# ProProject_IR_sensor_board_2024-06-21.net
KiCad netlist of a schematic drawn in EasyEDA Pro
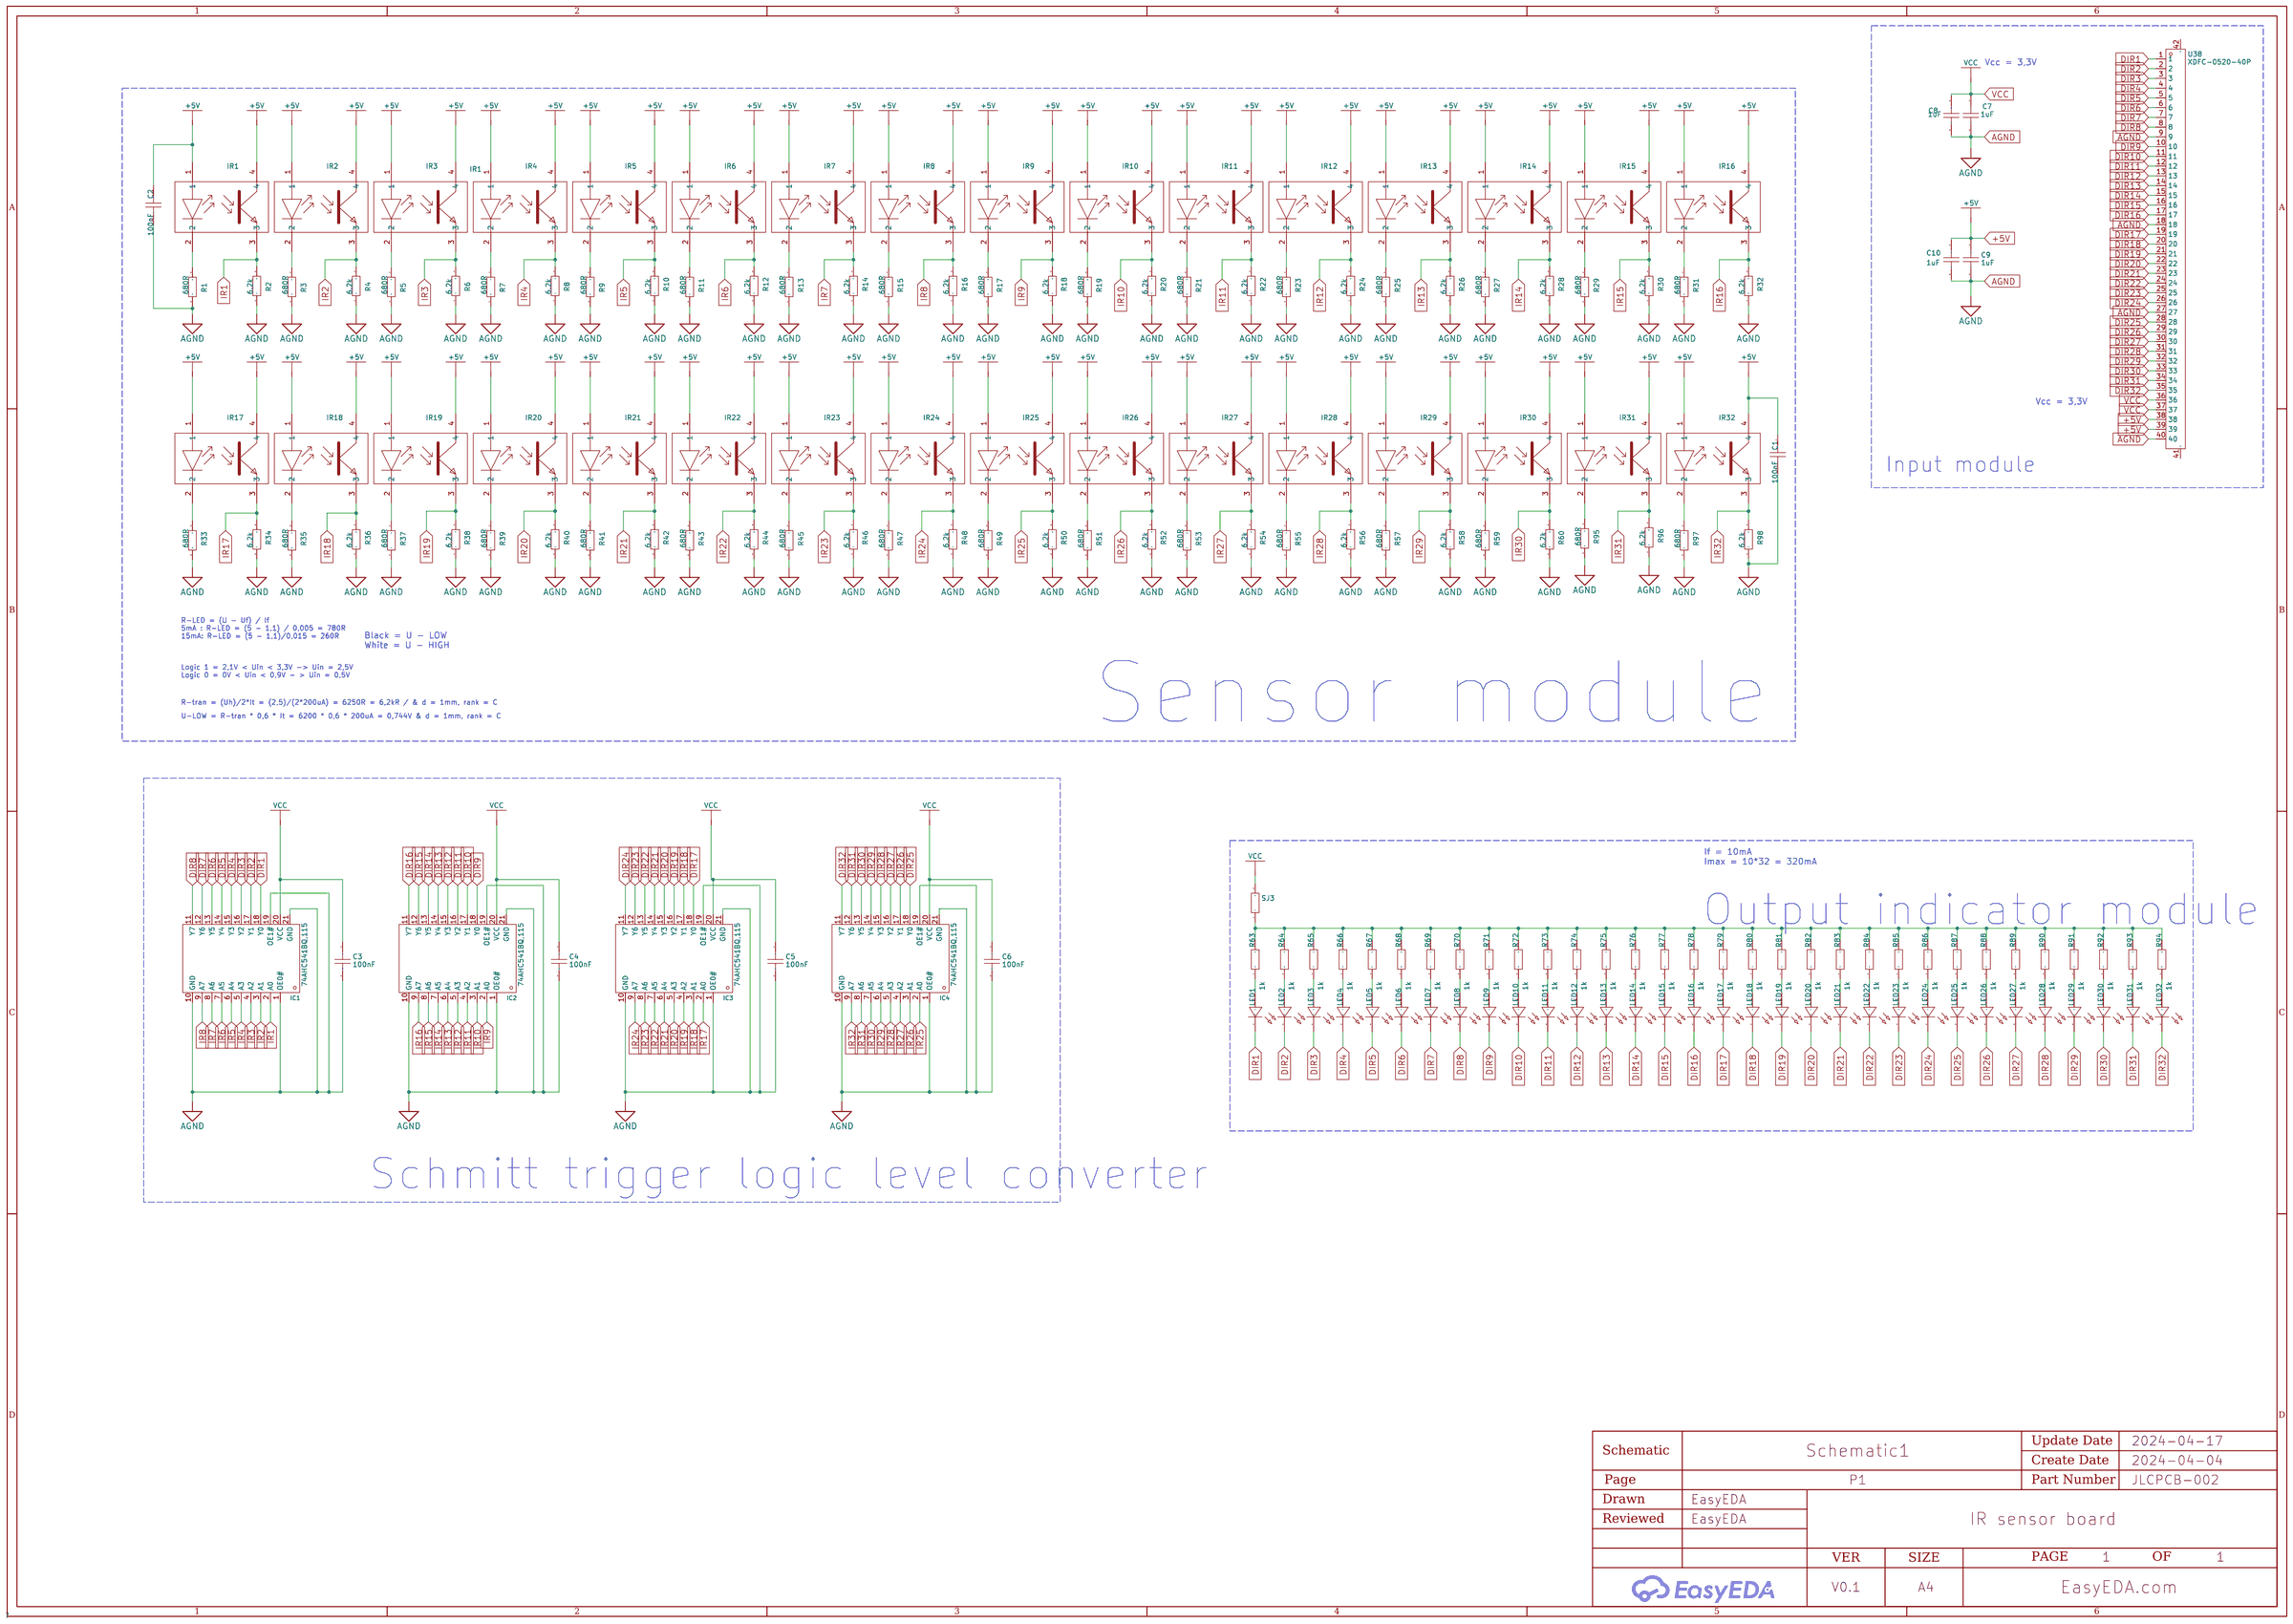
[diagram p0: schematic sheet]

(export (version "E")
  (design (tool "Eeschema 10.0.6"))
  (components
    (comp (ref "C1")
      (value "100nF")
      (footprint "easyedapro:C0603")
      (libsource (lib "easyedapro") (part "CAP"))
    )
    (comp (ref "C2")
      (value "100nF")
      (footprint "easyedapro:C0603")
      (libsource (lib "easyedapro") (part "CAP"))
    )
    (comp (ref "C3")
      (value "100nF")
      (footprint "easyedapro:C0603")
      (libsource (lib "easyedapro") (part "CAP"))
    )
    (comp (ref "C4")
      (value "100nF")
      (footprint "easyedapro:C0603")
      (libsource (lib "easyedapro") (part "CAP"))
    )
    (comp (ref "C5")
      (value "100nF")
      (footprint "easyedapro:C0603")
      (libsource (lib "easyedapro") (part "CAP"))
    )
    (comp (ref "C6")
      (value "100nF")
      (footprint "easyedapro:C0603")
      (libsource (lib "easyedapro") (part "CAP"))
    )
    (comp (ref "C7") (value "1uF") (footprint "easyedapro:C0603") (libsource (lib "easyedapro") (part "CAP")))
    (comp (ref "C8") (value "1uF") (footprint "easyedapro:C0603") (libsource (lib "easyedapro") (part "CAP")))
    (comp (ref "C9") (value "1uF") (footprint "easyedapro:C0603") (libsource (lib "easyedapro") (part "CAP")))
    (comp (ref "C10")
      (value "1uF")
      (footprint "easyedapro:C0603")
      (libsource (lib "easyedapro") (part "CAP"))
    )
    (comp (ref "IC1")
      (value "74AHC541BQ,115")
      (footprint "easyedapro:DHVQFN20_L4.5-W2.5-P0.50-BL-EP")
      (fields (field (name "Manufacturer") "Nexperia(安世)"))
      (libsource (lib "easyedapro") (part "74AHC541BQ,115"))
    )
    (comp (ref "IC2")
      (value "74AHC541BQ,115")
      (footprint "easyedapro:DHVQFN20_L4.5-W2.5-P0.50-BL-EP")
      (fields (field (name "Manufacturer") "Nexperia(安世)"))
      (libsource (lib "easyedapro") (part "74AHC541BQ,115"))
    )
    (comp (ref "IC3")
      (value "74AHC541BQ,115")
      (footprint "easyedapro:DHVQFN20_L4.5-W2.5-P0.50-BL-EP")
      (fields (field (name "Manufacturer") "Nexperia(安世)"))
      (libsource (lib "easyedapro") (part "74AHC541BQ,115"))
    )
    (comp (ref "IC4")
      (value "74AHC541BQ,115")
      (footprint "easyedapro:DHVQFN20_L4.5-W2.5-P0.50-BL-EP")
      (fields (field (name "Manufacturer") "Nexperia(安世)"))
      (libsource (lib "easyedapro") (part "74AHC541BQ,115"))
    )
    (comp (ref "IR1")
      (value "~")
      (footprint "easyedapro:KU163")
      (description "IR reflection sensor")
      (libsource (lib "easyedapro") (part "KU163"))
    )
    (comp (ref "IR2")
      (value "~")
      (footprint "easyedapro:KU163")
      (description "IR reflection sensor")
      (libsource (lib "easyedapro") (part "KU163"))
    )
    (comp (ref "IR3")
      (value "IR1")
      (footprint "easyedapro:KU163")
      (description "IR reflection sensor")
      (libsource (lib "easyedapro") (part "KU163"))
    )
    (comp (ref "IR4")
      (value "~")
      (footprint "easyedapro:KU163")
      (description "IR reflection sensor")
      (libsource (lib "easyedapro") (part "KU163"))
    )
    (comp (ref "IR5")
      (value "~")
      (footprint "easyedapro:KU163")
      (description "IR reflection sensor")
      (libsource (lib "easyedapro") (part "KU163"))
    )
    (comp (ref "IR6")
      (value "~")
      (footprint "easyedapro:KU163")
      (description "IR reflection sensor")
      (libsource (lib "easyedapro") (part "KU163"))
    )
    (comp (ref "IR7")
      (value "~")
      (footprint "easyedapro:KU163")
      (description "IR reflection sensor")
      (libsource (lib "easyedapro") (part "KU163"))
    )
    (comp (ref "IR8")
      (value "~")
      (footprint "easyedapro:KU163")
      (description "IR reflection sensor")
      (libsource (lib "easyedapro") (part "KU163"))
    )
    (comp (ref "IR9")
      (value "~")
      (footprint "easyedapro:KU163")
      (description "IR reflection sensor")
      (libsource (lib "easyedapro") (part "KU163"))
    )
    (comp (ref "IR10")
      (value "~")
      (footprint "easyedapro:KU163")
      (description "IR reflection sensor")
      (libsource (lib "easyedapro") (part "KU163"))
    )
    (comp (ref "IR11")
      (value "~")
      (footprint "easyedapro:KU163")
      (description "IR reflection sensor")
      (libsource (lib "easyedapro") (part "KU163"))
    )
    (comp (ref "IR12")
      (value "~")
      (footprint "easyedapro:KU163")
      (description "IR reflection sensor")
      (libsource (lib "easyedapro") (part "KU163"))
    )
    (comp (ref "IR13")
      (value "~")
      (footprint "easyedapro:KU163")
      (description "IR reflection sensor")
      (libsource (lib "easyedapro") (part "KU163"))
    )
    (comp (ref "IR14")
      (value "~")
      (footprint "easyedapro:KU163")
      (description "IR reflection sensor")
      (libsource (lib "easyedapro") (part "KU163"))
    )
    (comp (ref "IR15")
      (value "~")
      (footprint "easyedapro:KU163")
      (description "IR reflection sensor")
      (libsource (lib "easyedapro") (part "KU163"))
    )
    (comp (ref "IR16")
      (value "~")
      (footprint "easyedapro:KU163")
      (description "IR reflection sensor")
      (libsource (lib "easyedapro") (part "KU163"))
    )
    (comp (ref "IR17")
      (value "~")
      (footprint "easyedapro:KU163")
      (description "IR reflection sensor")
      (libsource (lib "easyedapro") (part "KU163"))
    )
    (comp (ref "IR18")
      (value "~")
      (footprint "easyedapro:KU163")
      (description "IR reflection sensor")
      (libsource (lib "easyedapro") (part "KU163"))
    )
    (comp (ref "IR19")
      (value "~")
      (footprint "easyedapro:KU163")
      (description "IR reflection sensor")
      (libsource (lib "easyedapro") (part "KU163"))
    )
    (comp (ref "IR20")
      (value "~")
      (footprint "easyedapro:KU163")
      (description "IR reflection sensor")
      (libsource (lib "easyedapro") (part "KU163"))
    )
    (comp (ref "IR21")
      (value "~")
      (footprint "easyedapro:KU163")
      (description "IR reflection sensor")
      (libsource (lib "easyedapro") (part "KU163"))
    )
    (comp (ref "IR22")
      (value "~")
      (footprint "easyedapro:KU163")
      (description "IR reflection sensor")
      (libsource (lib "easyedapro") (part "KU163"))
    )
    (comp (ref "IR23")
      (value "~")
      (footprint "easyedapro:KU163")
      (description "IR reflection sensor")
      (libsource (lib "easyedapro") (part "KU163"))
    )
    (comp (ref "IR24")
      (value "~")
      (footprint "easyedapro:KU163")
      (description "IR reflection sensor")
      (libsource (lib "easyedapro") (part "KU163"))
    )
    (comp (ref "IR25")
      (value "~")
      (footprint "easyedapro:KU163")
      (description "IR reflection sensor")
      (libsource (lib "easyedapro") (part "KU163"))
    )
    (comp (ref "IR26")
      (value "~")
      (footprint "easyedapro:KU163")
      (description "IR reflection sensor")
      (libsource (lib "easyedapro") (part "KU163"))
    )
    (comp (ref "IR27")
      (value "~")
      (footprint "easyedapro:KU163")
      (description "IR reflection sensor")
      (libsource (lib "easyedapro") (part "KU163"))
    )
    (comp (ref "IR28")
      (value "~")
      (footprint "easyedapro:KU163")
      (description "IR reflection sensor")
      (libsource (lib "easyedapro") (part "KU163"))
    )
    (comp (ref "IR29")
      (value "~")
      (footprint "easyedapro:KU163")
      (description "IR reflection sensor")
      (libsource (lib "easyedapro") (part "KU163"))
    )
    (comp (ref "IR30")
      (value "~")
      (footprint "easyedapro:KU163")
      (description "IR reflection sensor")
      (libsource (lib "easyedapro") (part "KU163"))
    )
    (comp (ref "IR31")
      (value "~")
      (footprint "easyedapro:KU163")
      (description "IR reflection sensor")
      (libsource (lib "easyedapro") (part "KU163"))
    )
    (comp (ref "IR32")
      (value "~")
      (footprint "easyedapro:KU163")
      (description "IR reflection sensor")
      (libsource (lib "easyedapro") (part "KU163"))
    )
    (comp (ref "LED1")
      (value "~")
      (footprint "easyedapro:LED0805-RD_GREEN")
      (libsource (lib "easyedapro") (part "LED_G"))
    )
    (comp (ref "LED2")
      (value "~")
      (footprint "easyedapro:LED0805-RD_GREEN")
      (libsource (lib "easyedapro") (part "LED_G"))
    )
    (comp (ref "LED3")
      (value "~")
      (footprint "easyedapro:LED0805-RD_GREEN")
      (libsource (lib "easyedapro") (part "LED_G"))
    )
    (comp (ref "LED4")
      (value "~")
      (footprint "easyedapro:LED0805-RD_GREEN")
      (libsource (lib "easyedapro") (part "LED_G"))
    )
    (comp (ref "LED5")
      (value "~")
      (footprint "easyedapro:LED0805-RD_GREEN")
      (libsource (lib "easyedapro") (part "LED_G"))
    )
    (comp (ref "LED6")
      (value "~")
      (footprint "easyedapro:LED0805-RD_GREEN")
      (libsource (lib "easyedapro") (part "LED_G"))
    )
    (comp (ref "LED7")
      (value "~")
      (footprint "easyedapro:LED0805-RD_GREEN")
      (libsource (lib "easyedapro") (part "LED_G"))
    )
    (comp (ref "LED8")
      (value "~")
      (footprint "easyedapro:LED0805-RD_GREEN")
      (libsource (lib "easyedapro") (part "LED_G"))
    )
    (comp (ref "LED9")
      (value "~")
      (footprint "easyedapro:LED0805-RD_GREEN")
      (libsource (lib "easyedapro") (part "LED_G"))
    )
    (comp (ref "LED10")
      (value "~")
      (footprint "easyedapro:LED0805-RD_GREEN")
      (libsource (lib "easyedapro") (part "LED_G"))
    )
    (comp (ref "LED11")
      (value "~")
      (footprint "easyedapro:LED0805-RD_GREEN")
      (libsource (lib "easyedapro") (part "LED_G"))
    )
    (comp (ref "LED12")
      (value "~")
      (footprint "easyedapro:LED0805-RD_GREEN")
      (libsource (lib "easyedapro") (part "LED_G"))
    )
    (comp (ref "LED13")
      (value "~")
      (footprint "easyedapro:LED0805-RD_GREEN")
      (libsource (lib "easyedapro") (part "LED_G"))
    )
    (comp (ref "LED14")
      (value "~")
      (footprint "easyedapro:LED0805-RD_GREEN")
      (libsource (lib "easyedapro") (part "LED_G"))
    )
    (comp (ref "LED15")
      (value "~")
      (footprint "easyedapro:LED0805-RD_GREEN")
      (libsource (lib "easyedapro") (part "LED_G"))
    )
    (comp (ref "LED16")
      (value "~")
      (footprint "easyedapro:LED0805-RD_GREEN")
      (libsource (lib "easyedapro") (part "LED_G"))
    )
    (comp (ref "LED17")
      (value "~")
      (footprint "easyedapro:LED0805-RD_GREEN")
      (libsource (lib "easyedapro") (part "LED_G"))
    )
    (comp (ref "LED18")
      (value "~")
      (footprint "easyedapro:LED0805-RD_GREEN")
      (libsource (lib "easyedapro") (part "LED_G"))
    )
    (comp (ref "LED19")
      (value "~")
      (footprint "easyedapro:LED0805-RD_GREEN")
      (libsource (lib "easyedapro") (part "LED_G"))
    )
    (comp (ref "LED20")
      (value "~")
      (footprint "easyedapro:LED0805-RD_GREEN")
      (libsource (lib "easyedapro") (part "LED_G"))
    )
    (comp (ref "LED21")
      (value "~")
      (footprint "easyedapro:LED0805-RD_GREEN")
      (libsource (lib "easyedapro") (part "LED_G"))
    )
    (comp (ref "LED22")
      (value "~")
      (footprint "easyedapro:LED0805-RD_GREEN")
      (libsource (lib "easyedapro") (part "LED_G"))
    )
    (comp (ref "LED23")
      (value "~")
      (footprint "easyedapro:LED0805-RD_GREEN")
      (libsource (lib "easyedapro") (part "LED_G"))
    )
    (comp (ref "LED24")
      (value "~")
      (footprint "easyedapro:LED0805-RD_GREEN")
      (libsource (lib "easyedapro") (part "LED_G"))
    )
    (comp (ref "LED25")
      (value "~")
      (footprint "easyedapro:LED0805-RD_GREEN")
      (libsource (lib "easyedapro") (part "LED_G"))
    )
    (comp (ref "LED26")
      (value "~")
      (footprint "easyedapro:LED0805-RD_GREEN")
      (libsource (lib "easyedapro") (part "LED_G"))
    )
    (comp (ref "LED27")
      (value "~")
      (footprint "easyedapro:LED0805-RD_GREEN")
      (libsource (lib "easyedapro") (part "LED_G"))
    )
    (comp (ref "LED28")
      (value "~")
      (footprint "easyedapro:LED0805-RD_GREEN")
      (libsource (lib "easyedapro") (part "LED_G"))
    )
    (comp (ref "LED29")
      (value "~")
      (footprint "easyedapro:LED0805-RD_GREEN")
      (libsource (lib "easyedapro") (part "LED_G"))
    )
    (comp (ref "LED30")
      (value "~")
      (footprint "easyedapro:LED0805-RD_GREEN")
      (libsource (lib "easyedapro") (part "LED_G"))
    )
    (comp (ref "LED31")
      (value "~")
      (footprint "easyedapro:LED0805-RD_GREEN")
      (libsource (lib "easyedapro") (part "LED_G"))
    )
    (comp (ref "LED32")
      (value "~")
      (footprint "easyedapro:LED0805-RD_GREEN")
      (libsource (lib "easyedapro") (part "LED_G"))
    )
    (comp (ref "R1")
      (value "680R")
      (footprint "easyedapro:R0603")
      (libsource (lib "easyedapro") (part "Res"))
    )
    (comp (ref "R2")
      (value "6.2k")
      (footprint "easyedapro:R0603")
      (libsource (lib "easyedapro") (part "Res"))
    )
    (comp (ref "R3")
      (value "680R")
      (footprint "easyedapro:R0603")
      (libsource (lib "easyedapro") (part "Res"))
    )
    (comp (ref "R4")
      (value "6.2k")
      (footprint "easyedapro:R0603")
      (libsource (lib "easyedapro") (part "Res"))
    )
    (comp (ref "R5")
      (value "680R")
      (footprint "easyedapro:R0603")
      (libsource (lib "easyedapro") (part "Res"))
    )
    (comp (ref "R6")
      (value "6.2k")
      (footprint "easyedapro:R0603")
      (libsource (lib "easyedapro") (part "Res"))
    )
    (comp (ref "R7")
      (value "680R")
      (footprint "easyedapro:R0603")
      (libsource (lib "easyedapro") (part "Res"))
    )
    (comp (ref "R8")
      (value "6.2k")
      (footprint "easyedapro:R0603")
      (libsource (lib "easyedapro") (part "Res"))
    )
    (comp (ref "R9")
      (value "680R")
      (footprint "easyedapro:R0603")
      (libsource (lib "easyedapro") (part "Res"))
    )
    (comp (ref "R10")
      (value "6.2k")
      (footprint "easyedapro:R0603")
      (libsource (lib "easyedapro") (part "Res"))
    )
    (comp (ref "R11")
      (value "680R")
      (footprint "easyedapro:R0603")
      (libsource (lib "easyedapro") (part "Res"))
    )
    (comp (ref "R12")
      (value "6.2k")
      (footprint "easyedapro:R0603")
      (libsource (lib "easyedapro") (part "Res"))
    )
    (comp (ref "R13")
      (value "680R")
      (footprint "easyedapro:R0603")
      (libsource (lib "easyedapro") (part "Res"))
    )
    (comp (ref "R14")
      (value "6.2k")
      (footprint "easyedapro:R0603")
      (libsource (lib "easyedapro") (part "Res"))
    )
    (comp (ref "R15")
      (value "680R")
      (footprint "easyedapro:R0603")
      (libsource (lib "easyedapro") (part "Res"))
    )
    (comp (ref "R16")
      (value "6.2k")
      (footprint "easyedapro:R0603")
      (libsource (lib "easyedapro") (part "Res"))
    )
    (comp (ref "R17")
      (value "680R")
      (footprint "easyedapro:R0603")
      (libsource (lib "easyedapro") (part "Res"))
    )
    (comp (ref "R18")
      (value "6.2k")
      (footprint "easyedapro:R0603")
      (libsource (lib "easyedapro") (part "Res"))
    )
    (comp (ref "R19")
      (value "680R")
      (footprint "easyedapro:R0603")
      (libsource (lib "easyedapro") (part "Res"))
    )
    (comp (ref "R20")
      (value "6.2k")
      (footprint "easyedapro:R0603")
      (libsource (lib "easyedapro") (part "Res"))
    )
    (comp (ref "R21")
      (value "680R")
      (footprint "easyedapro:R0603")
      (libsource (lib "easyedapro") (part "Res"))
    )
    (comp (ref "R22")
      (value "6.2k")
      (footprint "easyedapro:R0603")
      (libsource (lib "easyedapro") (part "Res"))
    )
    (comp (ref "R23")
      (value "680R")
      (footprint "easyedapro:R0603")
      (libsource (lib "easyedapro") (part "Res"))
    )
    (comp (ref "R24")
      (value "6.2k")
      (footprint "easyedapro:R0603")
      (libsource (lib "easyedapro") (part "Res"))
    )
    (comp (ref "R25")
      (value "680R")
      (footprint "easyedapro:R0603")
      (libsource (lib "easyedapro") (part "Res"))
    )
    (comp (ref "R26")
      (value "6.2k")
      (footprint "easyedapro:R0603")
      (libsource (lib "easyedapro") (part "Res"))
    )
    (comp (ref "R27")
      (value "680R")
      (footprint "easyedapro:R0603")
      (libsource (lib "easyedapro") (part "Res"))
    )
    (comp (ref "R28")
      (value "6.2k")
      (footprint "easyedapro:R0603")
      (libsource (lib "easyedapro") (part "Res"))
    )
    (comp (ref "R29")
      (value "680R")
      (footprint "easyedapro:R0603")
      (libsource (lib "easyedapro") (part "Res"))
    )
    (comp (ref "R30")
      (value "6.2k")
      (footprint "easyedapro:R0603")
      (libsource (lib "easyedapro") (part "Res"))
    )
    (comp (ref "R31")
      (value "680R")
      (footprint "easyedapro:R0603")
      (libsource (lib "easyedapro") (part "Res"))
    )
    (comp (ref "R32")
      (value "6.2k")
      (footprint "easyedapro:R0603")
      (libsource (lib "easyedapro") (part "Res"))
    )
    (comp (ref "R33")
      (value "680R")
      (footprint "easyedapro:R0603")
      (libsource (lib "easyedapro") (part "Res"))
    )
    (comp (ref "R34")
      (value "6.2k")
      (footprint "easyedapro:R0603")
      (libsource (lib "easyedapro") (part "Res"))
    )
    (comp (ref "R35")
      (value "680R")
      (footprint "easyedapro:R0603")
      (libsource (lib "easyedapro") (part "Res"))
    )
    (comp (ref "R36")
      (value "6.2k")
      (footprint "easyedapro:R0603")
      (libsource (lib "easyedapro") (part "Res"))
    )
    (comp (ref "R37")
      (value "680R")
      (footprint "easyedapro:R0603")
      (libsource (lib "easyedapro") (part "Res"))
    )
    (comp (ref "R38")
      (value "6.2k")
      (footprint "easyedapro:R0603")
      (libsource (lib "easyedapro") (part "Res"))
    )
    (comp (ref "R39")
      (value "680R")
      (footprint "easyedapro:R0603")
      (libsource (lib "easyedapro") (part "Res"))
    )
    (comp (ref "R40")
      (value "6.2k")
      (footprint "easyedapro:R0603")
      (libsource (lib "easyedapro") (part "Res"))
    )
    (comp (ref "R41")
      (value "680R")
      (footprint "easyedapro:R0603")
      (libsource (lib "easyedapro") (part "Res"))
    )
    (comp (ref "R42")
      (value "6.2k")
      (footprint "easyedapro:R0603")
      (libsource (lib "easyedapro") (part "Res"))
    )
    (comp (ref "R43")
      (value "680R")
      (footprint "easyedapro:R0603")
      (libsource (lib "easyedapro") (part "Res"))
    )
    (comp (ref "R44")
      (value "6.2k")
      (footprint "easyedapro:R0603")
      (libsource (lib "easyedapro") (part "Res"))
    )
    (comp (ref "R45")
      (value "680R")
      (footprint "easyedapro:R0603")
      (libsource (lib "easyedapro") (part "Res"))
    )
    (comp (ref "R46")
      (value "6.2k")
      (footprint "easyedapro:R0603")
      (libsource (lib "easyedapro") (part "Res"))
    )
    (comp (ref "R47")
      (value "680R")
      (footprint "easyedapro:R0603")
      (libsource (lib "easyedapro") (part "Res"))
    )
    (comp (ref "R48")
      (value "6.2k")
      (footprint "easyedapro:R0603")
      (libsource (lib "easyedapro") (part "Res"))
    )
    (comp (ref "R49")
      (value "680R")
      (footprint "easyedapro:R0603")
      (libsource (lib "easyedapro") (part "Res"))
    )
    (comp (ref "R50")
      (value "6.2k")
      (footprint "easyedapro:R0603")
      (libsource (lib "easyedapro") (part "Res"))
    )
    (comp (ref "R51")
      (value "680R")
      (footprint "easyedapro:R0603")
      (libsource (lib "easyedapro") (part "Res"))
    )
    (comp (ref "R52")
      (value "6.2k")
      (footprint "easyedapro:R0603")
      (libsource (lib "easyedapro") (part "Res"))
    )
    (comp (ref "R53")
      (value "680R")
      (footprint "easyedapro:R0603")
      (libsource (lib "easyedapro") (part "Res"))
    )
    (comp (ref "R54")
      (value "6.2k")
      (footprint "easyedapro:R0603")
      (libsource (lib "easyedapro") (part "Res"))
    )
    (comp (ref "R55")
      (value "680R")
      (footprint "easyedapro:R0603")
      (libsource (lib "easyedapro") (part "Res"))
    )
    (comp (ref "R56")
      (value "6.2k")
      (footprint "easyedapro:R0603")
      (libsource (lib "easyedapro") (part "Res"))
    )
    (comp (ref "R57")
      (value "680R")
      (footprint "easyedapro:R0603")
      (libsource (lib "easyedapro") (part "Res"))
    )
    (comp (ref "R58")
      (value "6.2k")
      (footprint "easyedapro:R0603")
      (libsource (lib "easyedapro") (part "Res"))
    )
    (comp (ref "R59")
      (value "680R")
      (footprint "easyedapro:R0603")
      (libsource (lib "easyedapro") (part "Res"))
    )
    (comp (ref "R60")
      (value "6.2k")
      (footprint "easyedapro:R0603")
      (libsource (lib "easyedapro") (part "Res"))
    )
    (comp (ref "R63") (value "1k") (footprint "easyedapro:R0603") (libsource (lib "easyedapro") (part "Res")))
    (comp (ref "R64") (value "1k") (footprint "easyedapro:R0603") (libsource (lib "easyedapro") (part "Res")))
    (comp (ref "R65") (value "1k") (footprint "easyedapro:R0603") (libsource (lib "easyedapro") (part "Res")))
    (comp (ref "R66") (value "1k") (footprint "easyedapro:R0603") (libsource (lib "easyedapro") (part "Res")))
    (comp (ref "R67") (value "1k") (footprint "easyedapro:R0603") (libsource (lib "easyedapro") (part "Res")))
    (comp (ref "R68") (value "1k") (footprint "easyedapro:R0603") (libsource (lib "easyedapro") (part "Res")))
    (comp (ref "R69") (value "1k") (footprint "easyedapro:R0603") (libsource (lib "easyedapro") (part "Res")))
    (comp (ref "R70") (value "1k") (footprint "easyedapro:R0603") (libsource (lib "easyedapro") (part "Res")))
    (comp (ref "R71") (value "1k") (footprint "easyedapro:R0603") (libsource (lib "easyedapro") (part "Res")))
    (comp (ref "R72") (value "1k") (footprint "easyedapro:R0603") (libsource (lib "easyedapro") (part "Res")))
    (comp (ref "R73") (value "1k") (footprint "easyedapro:R0603") (libsource (lib "easyedapro") (part "Res")))
    (comp (ref "R74") (value "1k") (footprint "easyedapro:R0603") (libsource (lib "easyedapro") (part "Res")))
    (comp (ref "R75") (value "1k") (footprint "easyedapro:R0603") (libsource (lib "easyedapro") (part "Res")))
    (comp (ref "R76") (value "1k") (footprint "easyedapro:R0603") (libsource (lib "easyedapro") (part "Res")))
    (comp (ref "R77") (value "1k") (footprint "easyedapro:R0603") (libsource (lib "easyedapro") (part "Res")))
    (comp (ref "R78") (value "1k") (footprint "easyedapro:R0603") (libsource (lib "easyedapro") (part "Res")))
    (comp (ref "R79") (value "1k") (footprint "easyedapro:R0603") (libsource (lib "easyedapro") (part "Res")))
    (comp (ref "R80") (value "1k") (footprint "easyedapro:R0603") (libsource (lib "easyedapro") (part "Res")))
    (comp (ref "R81") (value "1k") (footprint "easyedapro:R0603") (libsource (lib "easyedapro") (part "Res")))
    (comp (ref "R82") (value "1k") (footprint "easyedapro:R0603") (libsource (lib "easyedapro") (part "Res")))
    (comp (ref "R83") (value "1k") (footprint "easyedapro:R0603") (libsource (lib "easyedapro") (part "Res")))
    (comp (ref "R84") (value "1k") (footprint "easyedapro:R0603") (libsource (lib "easyedapro") (part "Res")))
    (comp (ref "R85") (value "1k") (footprint "easyedapro:R0603") (libsource (lib "easyedapro") (part "Res")))
    (comp (ref "R86") (value "1k") (footprint "easyedapro:R0603") (libsource (lib "easyedapro") (part "Res")))
    (comp (ref "R87") (value "1k") (footprint "easyedapro:R0603") (libsource (lib "easyedapro") (part "Res")))
    (comp (ref "R88") (value "1k") (footprint "easyedapro:R0603") (libsource (lib "easyedapro") (part "Res")))
    (comp (ref "R89") (value "1k") (footprint "easyedapro:R0603") (libsource (lib "easyedapro") (part "Res")))
    (comp (ref "R90") (value "1k") (footprint "easyedapro:R0603") (libsource (lib "easyedapro") (part "Res")))
    (comp (ref "R91") (value "1k") (footprint "easyedapro:R0603") (libsource (lib "easyedapro") (part "Res")))
    (comp (ref "R92") (value "1k") (footprint "easyedapro:R0603") (libsource (lib "easyedapro") (part "Res")))
    (comp (ref "R93") (value "1k") (footprint "easyedapro:R0603") (libsource (lib "easyedapro") (part "Res")))
    (comp (ref "R94") (value "1k") (footprint "easyedapro:R0603") (libsource (lib "easyedapro") (part "Res")))
    (comp (ref "R95")
      (value "680R")
      (footprint "easyedapro:R0603")
      (libsource (lib "easyedapro") (part "Res"))
    )
    (comp (ref "R96")
      (value "6.2k")
      (footprint "easyedapro:R0603")
      (libsource (lib "easyedapro") (part "Res"))
    )
    (comp (ref "R97")
      (value "680R")
      (footprint "easyedapro:R0603")
      (libsource (lib "easyedapro") (part "Res"))
    )
    (comp (ref "R98")
      (value "6.2k")
      (footprint "easyedapro:R0603")
      (libsource (lib "easyedapro") (part "Res"))
    )
    (comp (ref "SJ3")
      (value "10K")
      (footprint "easyedapro:R0603")
      (libsource (lib "easyedapro") (part "Res"))
    )
    (comp (ref "U38")
      (value "XDFC-0520-40P")
      (footprint "easyedapro:FPC-SMD_40P-P0.50_XDFC-0520-40P")
      (fields (field (name "Manufacturer") "LX(连欣科技)"))
      (libsource (lib "easyedapro") (part "XDFC-0520-40P"))
    )
  )
  (nets
    (net (code "1") (name "+5V") (class "Default")
      (node (ref "C1") (pin "1") (pinfunction "1_1") (pintype "input"))
      (node (ref "C10") (pin "1") (pinfunction "1_1") (pintype "input"))
      (node (ref "C2") (pin "1") (pinfunction "1_1") (pintype "input"))
      (node (ref "C9") (pin "1") (pinfunction "1_1") (pintype "input"))
      (node (ref "IR1") (pin "1") (pinfunction "1_1") (pintype "input"))
      (node (ref "IR1") (pin "4") (pinfunction "4_4") (pintype "input"))
      (node (ref "IR10") (pin "1") (pinfunction "1_1") (pintype "input"))
      (node (ref "IR10") (pin "4") (pinfunction "4_4") (pintype "input"))
      (node (ref "IR11") (pin "1") (pinfunction "1_1") (pintype "input"))
      (node (ref "IR11") (pin "4") (pinfunction "4_4") (pintype "input"))
      (node (ref "IR12") (pin "1") (pinfunction "1_1") (pintype "input"))
      (node (ref "IR12") (pin "4") (pinfunction "4_4") (pintype "input"))
      (node (ref "IR13") (pin "1") (pinfunction "1_1") (pintype "input"))
      (node (ref "IR13") (pin "4") (pinfunction "4_4") (pintype "input"))
      (node (ref "IR14") (pin "1") (pinfunction "1_1") (pintype "input"))
      (node (ref "IR14") (pin "4") (pinfunction "4_4") (pintype "input"))
      (node (ref "IR15") (pin "1") (pinfunction "1_1") (pintype "input"))
      (node (ref "IR15") (pin "4") (pinfunction "4_4") (pintype "input"))
      (node (ref "IR16") (pin "1") (pinfunction "1_1") (pintype "input"))
      (node (ref "IR16") (pin "4") (pinfunction "4_4") (pintype "input"))
      (node (ref "IR17") (pin "1") (pinfunction "1_1") (pintype "input"))
      (node (ref "IR17") (pin "4") (pinfunction "4_4") (pintype "input"))
      (node (ref "IR18") (pin "1") (pinfunction "1_1") (pintype "input"))
      (node (ref "IR18") (pin "4") (pinfunction "4_4") (pintype "input"))
      (node (ref "IR19") (pin "1") (pinfunction "1_1") (pintype "input"))
      (node (ref "IR19") (pin "4") (pinfunction "4_4") (pintype "input"))
      (node (ref "IR2") (pin "1") (pinfunction "1_1") (pintype "input"))
      (node (ref "IR2") (pin "4") (pinfunction "4_4") (pintype "input"))
      (node (ref "IR20") (pin "1") (pinfunction "1_1") (pintype "input"))
      (node (ref "IR20") (pin "4") (pinfunction "4_4") (pintype "input"))
      (node (ref "IR21") (pin "1") (pinfunction "1_1") (pintype "input"))
      (node (ref "IR21") (pin "4") (pinfunction "4_4") (pintype "input"))
      (node (ref "IR22") (pin "1") (pinfunction "1_1") (pintype "input"))
      (node (ref "IR22") (pin "4") (pinfunction "4_4") (pintype "input"))
      (node (ref "IR23") (pin "1") (pinfunction "1_1") (pintype "input"))
      (node (ref "IR23") (pin "4") (pinfunction "4_4") (pintype "input"))
      (node (ref "IR24") (pin "1") (pinfunction "1_1") (pintype "input"))
      (node (ref "IR24") (pin "4") (pinfunction "4_4") (pintype "input"))
      (node (ref "IR25") (pin "1") (pinfunction "1_1") (pintype "input"))
      (node (ref "IR25") (pin "4") (pinfunction "4_4") (pintype "input"))
      (node (ref "IR26") (pin "1") (pinfunction "1_1") (pintype "input"))
      (node (ref "IR26") (pin "4") (pinfunction "4_4") (pintype "input"))
      (node (ref "IR27") (pin "1") (pinfunction "1_1") (pintype "input"))
      (node (ref "IR27") (pin "4") (pinfunction "4_4") (pintype "input"))
      (node (ref "IR28") (pin "1") (pinfunction "1_1") (pintype "input"))
      (node (ref "IR28") (pin "4") (pinfunction "4_4") (pintype "input"))
      (node (ref "IR29") (pin "1") (pinfunction "1_1") (pintype "input"))
      (node (ref "IR29") (pin "4") (pinfunction "4_4") (pintype "input"))
      (node (ref "IR3") (pin "1") (pinfunction "1_1") (pintype "input"))
      (node (ref "IR3") (pin "4") (pinfunction "4_4") (pintype "input"))
      (node (ref "IR30") (pin "1") (pinfunction "1_1") (pintype "input"))
      (node (ref "IR30") (pin "4") (pinfunction "4_4") (pintype "input"))
      (node (ref "IR31") (pin "1") (pinfunction "1_1") (pintype "input"))
      (node (ref "IR31") (pin "4") (pinfunction "4_4") (pintype "input"))
      (node (ref "IR32") (pin "1") (pinfunction "1_1") (pintype "input"))
      (node (ref "IR32") (pin "4") (pinfunction "4_4") (pintype "input"))
      (node (ref "IR4") (pin "1") (pinfunction "1_1") (pintype "input"))
      (node (ref "IR4") (pin "4") (pinfunction "4_4") (pintype "input"))
      (node (ref "IR5") (pin "1") (pinfunction "1_1") (pintype "input"))
      (node (ref "IR5") (pin "4") (pinfunction "4_4") (pintype "input"))
      (node (ref "IR6") (pin "1") (pinfunction "1_1") (pintype "input"))
      (node (ref "IR6") (pin "4") (pinfunction "4_4") (pintype "input"))
      (node (ref "IR7") (pin "1") (pinfunction "1_1") (pintype "input"))
      (node (ref "IR7") (pin "4") (pinfunction "4_4") (pintype "input"))
      (node (ref "IR8") (pin "1") (pinfunction "1_1") (pintype "input"))
      (node (ref "IR8") (pin "4") (pinfunction "4_4") (pintype "input"))
      (node (ref "IR9") (pin "1") (pinfunction "1_1") (pintype "input"))
      (node (ref "IR9") (pin "4") (pinfunction "4_4") (pintype "input"))
      (node (ref "U38") (pin "38") (pinfunction "38_38") (pintype "unspecified"))
      (node (ref "U38") (pin "39") (pinfunction "39_39") (pintype "unspecified"))
    )
    (net (code "2") (name "AGND") (class "Default")
      (node (ref "C1") (pin "2") (pinfunction "2_2") (pintype "input"))
      (node (ref "C10") (pin "2") (pinfunction "2_2") (pintype "input"))
      (node (ref "C2") (pin "2") (pinfunction "2_2") (pintype "input"))
      (node (ref "C3") (pin "2") (pinfunction "2_2") (pintype "input"))
      (node (ref "C4") (pin "2") (pinfunction "2_2") (pintype "input"))
      (node (ref "C5") (pin "2") (pinfunction "2_2") (pintype "input"))
      (node (ref "C6") (pin "2") (pinfunction "2_2") (pintype "input"))
      (node (ref "C7") (pin "2") (pinfunction "2_2") (pintype "input"))
      (node (ref "C8") (pin "2") (pinfunction "2_2") (pintype "input"))
      (node (ref "C9") (pin "2") (pinfunction "2_2") (pintype "input"))
      (node (ref "IC1") (pin "1") (pinfunction "OE0#_1") (pintype "input"))
      (node (ref "IC1") (pin "10") (pinfunction "GND_10") (pintype "input"))
      (node (ref "IC1") (pin "19") (pinfunction "OE1#_19") (pintype "input"))
      (node (ref "IC1") (pin "21") (pinfunction "GND_21") (pintype "input"))
      (node (ref "IC2") (pin "1") (pinfunction "OE0#_1") (pintype "input"))
      (node (ref "IC2") (pin "10") (pinfunction "GND_10") (pintype "input"))
      (node (ref "IC2") (pin "19") (pinfunction "OE1#_19") (pintype "input"))
      (node (ref "IC2") (pin "21") (pinfunction "GND_21") (pintype "input"))
      (node (ref "IC3") (pin "1") (pinfunction "OE0#_1") (pintype "input"))
      (node (ref "IC3") (pin "10") (pinfunction "GND_10") (pintype "input"))
      (node (ref "IC3") (pin "19") (pinfunction "OE1#_19") (pintype "input"))
      (node (ref "IC3") (pin "21") (pinfunction "GND_21") (pintype "input"))
      (node (ref "IC4") (pin "1") (pinfunction "OE0#_1") (pintype "input"))
      (node (ref "IC4") (pin "10") (pinfunction "GND_10") (pintype "input"))
      (node (ref "IC4") (pin "19") (pinfunction "OE1#_19") (pintype "input"))
      (node (ref "IC4") (pin "21") (pinfunction "GND_21") (pintype "input"))
      (node (ref "R1") (pin "2") (pinfunction "2_2") (pintype "input"))
      (node (ref "R10") (pin "1") (pinfunction "1_1") (pintype "input"))
      (node (ref "R11") (pin "2") (pinfunction "2_2") (pintype "input"))
      (node (ref "R12") (pin "1") (pinfunction "1_1") (pintype "input"))
      (node (ref "R13") (pin "2") (pinfunction "2_2") (pintype "input"))
      (node (ref "R14") (pin "1") (pinfunction "1_1") (pintype "input"))
      (node (ref "R15") (pin "2") (pinfunction "2_2") (pintype "input"))
      (node (ref "R16") (pin "1") (pinfunction "1_1") (pintype "input"))
      (node (ref "R17") (pin "2") (pinfunction "2_2") (pintype "input"))
      (node (ref "R18") (pin "1") (pinfunction "1_1") (pintype "input"))
      (node (ref "R19") (pin "2") (pinfunction "2_2") (pintype "input"))
      (node (ref "R2") (pin "1") (pinfunction "1_1") (pintype "input"))
      (node (ref "R20") (pin "1") (pinfunction "1_1") (pintype "input"))
      (node (ref "R21") (pin "2") (pinfunction "2_2") (pintype "input"))
      (node (ref "R22") (pin "1") (pinfunction "1_1") (pintype "input"))
      (node (ref "R23") (pin "2") (pinfunction "2_2") (pintype "input"))
      (node (ref "R24") (pin "1") (pinfunction "1_1") (pintype "input"))
      (node (ref "R25") (pin "2") (pinfunction "2_2") (pintype "input"))
      (node (ref "R26") (pin "1") (pinfunction "1_1") (pintype "input"))
      (node (ref "R27") (pin "2") (pinfunction "2_2") (pintype "input"))
      (node (ref "R28") (pin "1") (pinfunction "1_1") (pintype "input"))
      (node (ref "R29") (pin "2") (pinfunction "2_2") (pintype "input"))
      (node (ref "R3") (pin "2") (pinfunction "2_2") (pintype "input"))
      (node (ref "R30") (pin "1") (pinfunction "1_1") (pintype "input"))
      (node (ref "R31") (pin "2") (pinfunction "2_2") (pintype "input"))
      (node (ref "R32") (pin "1") (pinfunction "1_1") (pintype "input"))
      (node (ref "R33") (pin "2") (pinfunction "2_2") (pintype "input"))
      (node (ref "R34") (pin "1") (pinfunction "1_1") (pintype "input"))
      (node (ref "R35") (pin "2") (pinfunction "2_2") (pintype "input"))
      (node (ref "R36") (pin "1") (pinfunction "1_1") (pintype "input"))
      (node (ref "R37") (pin "2") (pinfunction "2_2") (pintype "input"))
      (node (ref "R38") (pin "1") (pinfunction "1_1") (pintype "input"))
      (node (ref "R39") (pin "2") (pinfunction "2_2") (pintype "input"))
      (node (ref "R4") (pin "1") (pinfunction "1_1") (pintype "input"))
      (node (ref "R40") (pin "1") (pinfunction "1_1") (pintype "input"))
      (node (ref "R41") (pin "2") (pinfunction "2_2") (pintype "input"))
      (node (ref "R42") (pin "1") (pinfunction "1_1") (pintype "input"))
      (node (ref "R43") (pin "2") (pinfunction "2_2") (pintype "input"))
      (node (ref "R44") (pin "1") (pinfunction "1_1") (pintype "input"))
      (node (ref "R45") (pin "2") (pinfunction "2_2") (pintype "input"))
      (node (ref "R46") (pin "1") (pinfunction "1_1") (pintype "input"))
      (node (ref "R47") (pin "2") (pinfunction "2_2") (pintype "input"))
      (node (ref "R48") (pin "1") (pinfunction "1_1") (pintype "input"))
      (node (ref "R49") (pin "2") (pinfunction "2_2") (pintype "input"))
      (node (ref "R5") (pin "2") (pinfunction "2_2") (pintype "input"))
      (node (ref "R50") (pin "1") (pinfunction "1_1") (pintype "input"))
      (node (ref "R51") (pin "2") (pinfunction "2_2") (pintype "input"))
      (node (ref "R52") (pin "1") (pinfunction "1_1") (pintype "input"))
      (node (ref "R53") (pin "2") (pinfunction "2_2") (pintype "input"))
      (node (ref "R54") (pin "1") (pinfunction "1_1") (pintype "input"))
      (node (ref "R55") (pin "2") (pinfunction "2_2") (pintype "input"))
      (node (ref "R56") (pin "1") (pinfunction "1_1") (pintype "input"))
      (node (ref "R57") (pin "2") (pinfunction "2_2") (pintype "input"))
      (node (ref "R58") (pin "1") (pinfunction "1_1") (pintype "input"))
      (node (ref "R59") (pin "2") (pinfunction "2_2") (pintype "input"))
      (node (ref "R6") (pin "1") (pinfunction "1_1") (pintype "input"))
      (node (ref "R60") (pin "1") (pinfunction "1_1") (pintype "input"))
      (node (ref "R7") (pin "2") (pinfunction "2_2") (pintype "input"))
      (node (ref "R8") (pin "1") (pinfunction "1_1") (pintype "input"))
      (node (ref "R9") (pin "2") (pinfunction "2_2") (pintype "input"))
      (node (ref "R95") (pin "2") (pinfunction "2_2") (pintype "input"))
      (node (ref "R96") (pin "1") (pinfunction "1_1") (pintype "input"))
      (node (ref "R97") (pin "2") (pinfunction "2_2") (pintype "input"))
      (node (ref "R98") (pin "1") (pinfunction "1_1") (pintype "input"))
      (node (ref "U38") (pin "18") (pinfunction "18_18") (pintype "unspecified"))
      (node (ref "U38") (pin "27") (pinfunction "27_27") (pintype "unspecified"))
      (node (ref "U38") (pin "40") (pinfunction "40_40") (pintype "unspecified"))
      (node (ref "U38") (pin "9") (pinfunction "9_9") (pintype "unspecified"))
    )
    (net (code "3") (name "DIR1") (class "Default")
      (node (ref "IC1") (pin "18") (pinfunction "Y0_18") (pintype "input"))
      (node (ref "LED1") (pin "1") (pinfunction "C_1") (pintype "input"))
      (node (ref "U38") (pin "1") (pinfunction "1_1") (pintype "unspecified"))
    )
    (net (code "4") (name "DIR2") (class "Default")
      (node (ref "IC1") (pin "17") (pinfunction "Y1_17") (pintype "input"))
      (node (ref "LED2") (pin "1") (pinfunction "C_1") (pintype "input"))
      (node (ref "U38") (pin "2") (pinfunction "2_2") (pintype "unspecified"))
    )
    (net (code "5") (name "DIR3") (class "Default")
      (node (ref "IC1") (pin "16") (pinfunction "Y2_16") (pintype "input"))
      (node (ref "LED3") (pin "1") (pinfunction "C_1") (pintype "input"))
      (node (ref "U38") (pin "3") (pinfunction "3_3") (pintype "unspecified"))
    )
    (net (code "6") (name "DIR4") (class "Default")
      (node (ref "IC1") (pin "15") (pinfunction "Y3_15") (pintype "input"))
      (node (ref "LED4") (pin "1") (pinfunction "C_1") (pintype "input"))
      (node (ref "U38") (pin "4") (pinfunction "4_4") (pintype "unspecified"))
    )
    (net (code "7") (name "DIR5") (class "Default")
      (node (ref "IC1") (pin "14") (pinfunction "Y4_14") (pintype "input"))
      (node (ref "LED5") (pin "1") (pinfunction "C_1") (pintype "input"))
      (node (ref "U38") (pin "5") (pinfunction "5_5") (pintype "unspecified"))
    )
    (net (code "8") (name "DIR6") (class "Default")
      (node (ref "IC1") (pin "13") (pinfunction "Y5_13") (pintype "input"))
      (node (ref "LED6") (pin "1") (pinfunction "C_1") (pintype "input"))
      (node (ref "U38") (pin "6") (pinfunction "6_6") (pintype "unspecified"))
    )
    (net (code "9") (name "DIR7") (class "Default")
      (node (ref "IC1") (pin "12") (pinfunction "Y6_12") (pintype "input"))
      (node (ref "LED7") (pin "1") (pinfunction "C_1") (pintype "input"))
      (node (ref "U38") (pin "7") (pinfunction "7_7") (pintype "unspecified"))
    )
    (net (code "10") (name "DIR8") (class "Default")
      (node (ref "IC1") (pin "11") (pinfunction "Y7_11") (pintype "input"))
      (node (ref "LED8") (pin "1") (pinfunction "C_1") (pintype "input"))
      (node (ref "U38") (pin "8") (pinfunction "8_8") (pintype "unspecified"))
    )
    (net (code "11") (name "DIR9") (class "Default")
      (node (ref "IC2") (pin "18") (pinfunction "Y0_18") (pintype "input"))
      (node (ref "LED9") (pin "1") (pinfunction "C_1") (pintype "input"))
      (node (ref "U38") (pin "10") (pinfunction "10_10") (pintype "unspecified"))
    )
    (net (code "12") (name "DIR10") (class "Default")
      (node (ref "IC2") (pin "17") (pinfunction "Y1_17") (pintype "input"))
      (node (ref "LED10") (pin "1") (pinfunction "C_1") (pintype "input"))
      (node (ref "U38") (pin "11") (pinfunction "11_11") (pintype "unspecified"))
    )
    (net (code "13") (name "DIR11") (class "Default")
      (node (ref "IC2") (pin "16") (pinfunction "Y2_16") (pintype "input"))
      (node (ref "LED11") (pin "1") (pinfunction "C_1") (pintype "input"))
      (node (ref "U38") (pin "12") (pinfunction "12_12") (pintype "unspecified"))
    )
    (net (code "14") (name "DIR12") (class "Default")
      (node (ref "IC2") (pin "15") (pinfunction "Y3_15") (pintype "input"))
      (node (ref "LED12") (pin "1") (pinfunction "C_1") (pintype "input"))
      (node (ref "U38") (pin "13") (pinfunction "13_13") (pintype "unspecified"))
    )
    (net (code "15") (name "DIR13") (class "Default")
      (node (ref "IC2") (pin "14") (pinfunction "Y4_14") (pintype "input"))
      (node (ref "LED13") (pin "1") (pinfunction "C_1") (pintype "input"))
      (node (ref "U38") (pin "14") (pinfunction "14_14") (pintype "unspecified"))
    )
    (net (code "16") (name "DIR14") (class "Default")
      (node (ref "IC2") (pin "13") (pinfunction "Y5_13") (pintype "input"))
      (node (ref "LED14") (pin "1") (pinfunction "C_1") (pintype "input"))
      (node (ref "U38") (pin "15") (pinfunction "15_15") (pintype "unspecified"))
    )
    (net (code "17") (name "DIR15") (class "Default")
      (node (ref "IC2") (pin "12") (pinfunction "Y6_12") (pintype "input"))
      (node (ref "LED15") (pin "1") (pinfunction "C_1") (pintype "input"))
      (node (ref "U38") (pin "16") (pinfunction "16_16") (pintype "unspecified"))
    )
    (net (code "18") (name "DIR16") (class "Default")
      (node (ref "IC2") (pin "11") (pinfunction "Y7_11") (pintype "input"))
      (node (ref "LED16") (pin "1") (pinfunction "C_1") (pintype "input"))
      (node (ref "U38") (pin "17") (pinfunction "17_17") (pintype "unspecified"))
    )
    (net (code "19") (name "DIR17") (class "Default")
      (node (ref "IC3") (pin "18") (pinfunction "Y0_18") (pintype "input"))
      (node (ref "LED17") (pin "1") (pinfunction "C_1") (pintype "input"))
      (node (ref "U38") (pin "19") (pinfunction "19_19") (pintype "unspecified"))
    )
    (net (code "20") (name "DIR18") (class "Default")
      (node (ref "IC3") (pin "17") (pinfunction "Y1_17") (pintype "input"))
      (node (ref "LED18") (pin "1") (pinfunction "C_1") (pintype "input"))
      (node (ref "U38") (pin "20") (pinfunction "20_20") (pintype "unspecified"))
    )
    (net (code "21") (name "DIR19") (class "Default")
      (node (ref "IC3") (pin "16") (pinfunction "Y2_16") (pintype "input"))
      (node (ref "LED19") (pin "1") (pinfunction "C_1") (pintype "input"))
      (node (ref "U38") (pin "21") (pinfunction "21_21") (pintype "unspecified"))
    )
    (net (code "22") (name "DIR20") (class "Default")
      (node (ref "IC3") (pin "15") (pinfunction "Y3_15") (pintype "input"))
      (node (ref "LED20") (pin "1") (pinfunction "C_1") (pintype "input"))
      (node (ref "U38") (pin "22") (pinfunction "22_22") (pintype "unspecified"))
    )
    (net (code "23") (name "DIR21") (class "Default")
      (node (ref "IC3") (pin "14") (pinfunction "Y4_14") (pintype "input"))
      (node (ref "LED21") (pin "1") (pinfunction "C_1") (pintype "input"))
      (node (ref "U38") (pin "23") (pinfunction "23_23") (pintype "unspecified"))
    )
    (net (code "24") (name "DIR22") (class "Default")
      (node (ref "IC3") (pin "13") (pinfunction "Y5_13") (pintype "input"))
      (node (ref "LED22") (pin "1") (pinfunction "C_1") (pintype "input"))
      (node (ref "U38") (pin "24") (pinfunction "24_24") (pintype "unspecified"))
    )
    (net (code "25") (name "DIR23") (class "Default")
      (node (ref "IC3") (pin "12") (pinfunction "Y6_12") (pintype "input"))
      (node (ref "LED23") (pin "1") (pinfunction "C_1") (pintype "input"))
      (node (ref "U38") (pin "25") (pinfunction "25_25") (pintype "unspecified"))
    )
    (net (code "26") (name "DIR24") (class "Default")
      (node (ref "IC3") (pin "11") (pinfunction "Y7_11") (pintype "input"))
      (node (ref "LED24") (pin "1") (pinfunction "C_1") (pintype "input"))
      (node (ref "U38") (pin "26") (pinfunction "26_26") (pintype "unspecified"))
    )
    (net (code "27") (name "DIR25") (class "Default")
      (node (ref "IC4") (pin "18") (pinfunction "Y0_18") (pintype "input"))
      (node (ref "LED25") (pin "1") (pinfunction "C_1") (pintype "input"))
      (node (ref "U38") (pin "28") (pinfunction "28_28") (pintype "unspecified"))
    )
    (net (code "28") (name "DIR26") (class "Default")
      (node (ref "IC4") (pin "17") (pinfunction "Y1_17") (pintype "input"))
      (node (ref "LED26") (pin "1") (pinfunction "C_1") (pintype "input"))
      (node (ref "U38") (pin "29") (pinfunction "29_29") (pintype "unspecified"))
    )
    (net (code "29") (name "DIR27") (class "Default")
      (node (ref "IC4") (pin "16") (pinfunction "Y2_16") (pintype "input"))
      (node (ref "LED27") (pin "1") (pinfunction "C_1") (pintype "input"))
      (node (ref "U38") (pin "30") (pinfunction "30_30") (pintype "unspecified"))
    )
    (net (code "30") (name "DIR28") (class "Default")
      (node (ref "IC4") (pin "15") (pinfunction "Y3_15") (pintype "input"))
      (node (ref "LED28") (pin "1") (pinfunction "C_1") (pintype "input"))
      (node (ref "U38") (pin "31") (pinfunction "31_31") (pintype "unspecified"))
    )
    (net (code "31") (name "DIR29") (class "Default")
      (node (ref "IC4") (pin "14") (pinfunction "Y4_14") (pintype "input"))
      (node (ref "LED29") (pin "1") (pinfunction "C_1") (pintype "input"))
      (node (ref "U38") (pin "32") (pinfunction "32_32") (pintype "unspecified"))
    )
    (net (code "32") (name "DIR30") (class "Default")
      (node (ref "IC4") (pin "13") (pinfunction "Y5_13") (pintype "input"))
      (node (ref "LED30") (pin "1") (pinfunction "C_1") (pintype "input"))
      (node (ref "U38") (pin "33") (pinfunction "33_33") (pintype "unspecified"))
    )
    (net (code "33") (name "DIR31") (class "Default")
      (node (ref "IC4") (pin "12") (pinfunction "Y6_12") (pintype "input"))
      (node (ref "LED31") (pin "1") (pinfunction "C_1") (pintype "input"))
      (node (ref "U38") (pin "34") (pinfunction "34_34") (pintype "unspecified"))
    )
    (net (code "34") (name "DIR32") (class "Default")
      (node (ref "IC4") (pin "11") (pinfunction "Y7_11") (pintype "input"))
      (node (ref "LED32") (pin "1") (pinfunction "C_1") (pintype "input"))
      (node (ref "U38") (pin "35") (pinfunction "35_35") (pintype "unspecified"))
    )
    (net (code "35") (name "IR1") (class "Default")
      (node (ref "IC1") (pin "2") (pinfunction "A0_2") (pintype "input"))
      (node (ref "IR1") (pin "3") (pinfunction "3_3") (pintype "input"))
      (node (ref "R2") (pin "2") (pinfunction "2_2") (pintype "input"))
    )
    (net (code "36") (name "IR2") (class "Default")
      (node (ref "IC1") (pin "3") (pinfunction "A1_3") (pintype "input"))
      (node (ref "IR2") (pin "3") (pinfunction "3_3") (pintype "input"))
      (node (ref "R4") (pin "2") (pinfunction "2_2") (pintype "input"))
    )
    (net (code "37") (name "IR3") (class "Default")
      (node (ref "IC1") (pin "4") (pinfunction "A2_4") (pintype "input"))
      (node (ref "IR3") (pin "3") (pinfunction "3_3") (pintype "input"))
      (node (ref "R6") (pin "2") (pinfunction "2_2") (pintype "input"))
    )
    (net (code "38") (name "IR4") (class "Default")
      (node (ref "IC1") (pin "5") (pinfunction "A3_5") (pintype "input"))
      (node (ref "IR4") (pin "3") (pinfunction "3_3") (pintype "input"))
      (node (ref "R8") (pin "2") (pinfunction "2_2") (pintype "input"))
    )
    (net (code "39") (name "IR5") (class "Default")
      (node (ref "IC1") (pin "6") (pinfunction "A4_6") (pintype "input"))
      (node (ref "IR5") (pin "3") (pinfunction "3_3") (pintype "input"))
      (node (ref "R10") (pin "2") (pinfunction "2_2") (pintype "input"))
    )
    (net (code "40") (name "IR6") (class "Default")
      (node (ref "IC1") (pin "7") (pinfunction "A5_7") (pintype "input"))
      (node (ref "IR6") (pin "3") (pinfunction "3_3") (pintype "input"))
      (node (ref "R12") (pin "2") (pinfunction "2_2") (pintype "input"))
    )
    (net (code "41") (name "IR7") (class "Default")
      (node (ref "IC1") (pin "8") (pinfunction "A6_8") (pintype "input"))
      (node (ref "IR7") (pin "3") (pinfunction "3_3") (pintype "input"))
      (node (ref "R14") (pin "2") (pinfunction "2_2") (pintype "input"))
    )
    (net (code "42") (name "IR8") (class "Default")
      (node (ref "IC1") (pin "9") (pinfunction "A7_9") (pintype "input"))
      (node (ref "IR8") (pin "3") (pinfunction "3_3") (pintype "input"))
      (node (ref "R16") (pin "2") (pinfunction "2_2") (pintype "input"))
    )
    (net (code "43") (name "IR9") (class "Default")
      (node (ref "IC2") (pin "2") (pinfunction "A0_2") (pintype "input"))
      (node (ref "IR9") (pin "3") (pinfunction "3_3") (pintype "input"))
      (node (ref "R18") (pin "2") (pinfunction "2_2") (pintype "input"))
    )
    (net (code "44") (name "IR10") (class "Default")
      (node (ref "IC2") (pin "3") (pinfunction "A1_3") (pintype "input"))
      (node (ref "IR10") (pin "3") (pinfunction "3_3") (pintype "input"))
      (node (ref "R20") (pin "2") (pinfunction "2_2") (pintype "input"))
    )
    (net (code "45") (name "IR11") (class "Default")
      (node (ref "IC2") (pin "4") (pinfunction "A2_4") (pintype "input"))
      (node (ref "IR11") (pin "3") (pinfunction "3_3") (pintype "input"))
      (node (ref "R22") (pin "2") (pinfunction "2_2") (pintype "input"))
    )
    (net (code "46") (name "IR12") (class "Default")
      (node (ref "IC2") (pin "5") (pinfunction "A3_5") (pintype "input"))
      (node (ref "IR12") (pin "3") (pinfunction "3_3") (pintype "input"))
      (node (ref "R24") (pin "2") (pinfunction "2_2") (pintype "input"))
    )
    (net (code "47") (name "IR13") (class "Default")
      (node (ref "IC2") (pin "6") (pinfunction "A4_6") (pintype "input"))
      (node (ref "IR13") (pin "3") (pinfunction "3_3") (pintype "input"))
      (node (ref "R26") (pin "2") (pinfunction "2_2") (pintype "input"))
    )
    (net (code "48") (name "IR14") (class "Default")
      (node (ref "IC2") (pin "7") (pinfunction "A5_7") (pintype "input"))
      (node (ref "IR14") (pin "3") (pinfunction "3_3") (pintype "input"))
      (node (ref "R28") (pin "2") (pinfunction "2_2") (pintype "input"))
    )
    (net (code "49") (name "IR15") (class "Default")
      (node (ref "IC2") (pin "8") (pinfunction "A6_8") (pintype "input"))
      (node (ref "IR15") (pin "3") (pinfunction "3_3") (pintype "input"))
      (node (ref "R30") (pin "2") (pinfunction "2_2") (pintype "input"))
    )
    (net (code "50") (name "IR16") (class "Default")
      (node (ref "IC2") (pin "9") (pinfunction "A7_9") (pintype "input"))
      (node (ref "IR16") (pin "3") (pinfunction "3_3") (pintype "input"))
      (node (ref "R32") (pin "2") (pinfunction "2_2") (pintype "input"))
    )
    (net (code "51") (name "IR17") (class "Default")
      (node (ref "IC3") (pin "2") (pinfunction "A0_2") (pintype "input"))
      (node (ref "IR17") (pin "3") (pinfunction "3_3") (pintype "input"))
      (node (ref "R34") (pin "2") (pinfunction "2_2") (pintype "input"))
    )
    (net (code "52") (name "IR18") (class "Default")
      (node (ref "IC3") (pin "3") (pinfunction "A1_3") (pintype "input"))
      (node (ref "IR18") (pin "3") (pinfunction "3_3") (pintype "input"))
      (node (ref "R36") (pin "2") (pinfunction "2_2") (pintype "input"))
    )
    (net (code "53") (name "IR19") (class "Default")
      (node (ref "IC3") (pin "4") (pinfunction "A2_4") (pintype "input"))
      (node (ref "IR19") (pin "3") (pinfunction "3_3") (pintype "input"))
      (node (ref "R38") (pin "2") (pinfunction "2_2") (pintype "input"))
    )
    (net (code "54") (name "IR20") (class "Default")
      (node (ref "IC3") (pin "5") (pinfunction "A3_5") (pintype "input"))
      (node (ref "IR20") (pin "3") (pinfunction "3_3") (pintype "input"))
      (node (ref "R40") (pin "2") (pinfunction "2_2") (pintype "input"))
    )
    (net (code "55") (name "IR21") (class "Default")
      (node (ref "IC3") (pin "6") (pinfunction "A4_6") (pintype "input"))
      (node (ref "IR21") (pin "3") (pinfunction "3_3") (pintype "input"))
      (node (ref "R42") (pin "2") (pinfunction "2_2") (pintype "input"))
    )
    (net (code "56") (name "IR22") (class "Default")
      (node (ref "IC3") (pin "7") (pinfunction "A5_7") (pintype "input"))
      (node (ref "IR22") (pin "3") (pinfunction "3_3") (pintype "input"))
      (node (ref "R44") (pin "2") (pinfunction "2_2") (pintype "input"))
    )
    (net (code "57") (name "IR23") (class "Default")
      (node (ref "IC3") (pin "8") (pinfunction "A6_8") (pintype "input"))
      (node (ref "IR23") (pin "3") (pinfunction "3_3") (pintype "input"))
      (node (ref "R46") (pin "2") (pinfunction "2_2") (pintype "input"))
    )
    (net (code "58") (name "IR24") (class "Default")
      (node (ref "IC3") (pin "9") (pinfunction "A7_9") (pintype "input"))
      (node (ref "IR24") (pin "3") (pinfunction "3_3") (pintype "input"))
      (node (ref "R48") (pin "2") (pinfunction "2_2") (pintype "input"))
    )
    (net (code "59") (name "IR25") (class "Default")
      (node (ref "IC4") (pin "2") (pinfunction "A0_2") (pintype "input"))
      (node (ref "IR25") (pin "3") (pinfunction "3_3") (pintype "input"))
      (node (ref "R50") (pin "2") (pinfunction "2_2") (pintype "input"))
    )
    (net (code "60") (name "IR26") (class "Default")
      (node (ref "IC4") (pin "3") (pinfunction "A1_3") (pintype "input"))
      (node (ref "IR26") (pin "3") (pinfunction "3_3") (pintype "input"))
      (node (ref "R52") (pin "2") (pinfunction "2_2") (pintype "input"))
    )
    (net (code "61") (name "IR27") (class "Default")
      (node (ref "IC4") (pin "4") (pinfunction "A2_4") (pintype "input"))
      (node (ref "IR27") (pin "3") (pinfunction "3_3") (pintype "input"))
      (node (ref "R54") (pin "2") (pinfunction "2_2") (pintype "input"))
    )
    (net (code "62") (name "IR28") (class "Default")
      (node (ref "IC4") (pin "5") (pinfunction "A3_5") (pintype "input"))
      (node (ref "IR28") (pin "3") (pinfunction "3_3") (pintype "input"))
      (node (ref "R56") (pin "2") (pinfunction "2_2") (pintype "input"))
    )
    (net (code "63") (name "IR29") (class "Default")
      (node (ref "IC4") (pin "6") (pinfunction "A4_6") (pintype "input"))
      (node (ref "IR29") (pin "3") (pinfunction "3_3") (pintype "input"))
      (node (ref "R58") (pin "2") (pinfunction "2_2") (pintype "input"))
    )
    (net (code "64") (name "IR30") (class "Default")
      (node (ref "IC4") (pin "7") (pinfunction "A5_7") (pintype "input"))
      (node (ref "IR30") (pin "3") (pinfunction "3_3") (pintype "input"))
      (node (ref "R60") (pin "2") (pinfunction "2_2") (pintype "input"))
    )
    (net (code "65") (name "IR31") (class "Default")
      (node (ref "IC4") (pin "8") (pinfunction "A6_8") (pintype "input"))
      (node (ref "IR31") (pin "3") (pinfunction "3_3") (pintype "input"))
      (node (ref "R96") (pin "2") (pinfunction "2_2") (pintype "input"))
    )
    (net (code "66") (name "IR32") (class "Default")
      (node (ref "IC4") (pin "9") (pinfunction "A7_9") (pintype "input"))
      (node (ref "IR32") (pin "3") (pinfunction "3_3") (pintype "input"))
      (node (ref "R98") (pin "2") (pinfunction "2_2") (pintype "input"))
    )
    (net (code "67") (name "Net-(IR1-Pad2)") (class "Default")
      (node (ref "IR1") (pin "2") (pinfunction "2_2") (pintype "input"))
      (node (ref "R1") (pin "1") (pinfunction "1_1") (pintype "input"))
    )
    (net (code "68") (name "Net-(IR2-Pad2)") (class "Default")
      (node (ref "IR2") (pin "2") (pinfunction "2_2") (pintype "input"))
      (node (ref "R3") (pin "1") (pinfunction "1_1") (pintype "input"))
    )
    (net (code "69") (name "Net-(IR3-Pad2)") (class "Default")
      (node (ref "IR3") (pin "2") (pinfunction "2_2") (pintype "input"))
      (node (ref "R5") (pin "1") (pinfunction "1_1") (pintype "input"))
    )
    (net (code "70") (name "Net-(IR4-Pad2)") (class "Default")
      (node (ref "IR4") (pin "2") (pinfunction "2_2") (pintype "input"))
      (node (ref "R7") (pin "1") (pinfunction "1_1") (pintype "input"))
    )
    (net (code "71") (name "Net-(IR5-Pad2)") (class "Default")
      (node (ref "IR5") (pin "2") (pinfunction "2_2") (pintype "input"))
      (node (ref "R9") (pin "1") (pinfunction "1_1") (pintype "input"))
    )
    (net (code "72") (name "Net-(IR6-Pad2)") (class "Default")
      (node (ref "IR6") (pin "2") (pinfunction "2_2") (pintype "input"))
      (node (ref "R11") (pin "1") (pinfunction "1_1") (pintype "input"))
    )
    (net (code "73") (name "Net-(IR7-Pad2)") (class "Default")
      (node (ref "IR7") (pin "2") (pinfunction "2_2") (pintype "input"))
      (node (ref "R13") (pin "1") (pinfunction "1_1") (pintype "input"))
    )
    (net (code "74") (name "Net-(IR8-Pad2)") (class "Default")
      (node (ref "IR8") (pin "2") (pinfunction "2_2") (pintype "input"))
      (node (ref "R15") (pin "1") (pinfunction "1_1") (pintype "input"))
    )
    (net (code "75") (name "Net-(IR9-Pad2)") (class "Default")
      (node (ref "IR9") (pin "2") (pinfunction "2_2") (pintype "input"))
      (node (ref "R17") (pin "1") (pinfunction "1_1") (pintype "input"))
    )
    (net (code "76") (name "Net-(IR10-Pad2)") (class "Default")
      (node (ref "IR10") (pin "2") (pinfunction "2_2") (pintype "input"))
      (node (ref "R19") (pin "1") (pinfunction "1_1") (pintype "input"))
    )
    (net (code "77") (name "Net-(IR11-Pad2)") (class "Default")
      (node (ref "IR11") (pin "2") (pinfunction "2_2") (pintype "input"))
      (node (ref "R21") (pin "1") (pinfunction "1_1") (pintype "input"))
    )
    (net (code "78") (name "Net-(IR12-Pad2)") (class "Default")
      (node (ref "IR12") (pin "2") (pinfunction "2_2") (pintype "input"))
      (node (ref "R23") (pin "1") (pinfunction "1_1") (pintype "input"))
    )
    (net (code "79") (name "Net-(IR13-Pad2)") (class "Default")
      (node (ref "IR13") (pin "2") (pinfunction "2_2") (pintype "input"))
      (node (ref "R25") (pin "1") (pinfunction "1_1") (pintype "input"))
    )
    (net (code "80") (name "Net-(IR14-Pad2)") (class "Default")
      (node (ref "IR14") (pin "2") (pinfunction "2_2") (pintype "input"))
      (node (ref "R27") (pin "1") (pinfunction "1_1") (pintype "input"))
    )
    (net (code "81") (name "Net-(IR15-Pad2)") (class "Default")
      (node (ref "IR15") (pin "2") (pinfunction "2_2") (pintype "input"))
      (node (ref "R29") (pin "1") (pinfunction "1_1") (pintype "input"))
    )
    (net (code "82") (name "Net-(IR16-Pad2)") (class "Default")
      (node (ref "IR16") (pin "2") (pinfunction "2_2") (pintype "input"))
      (node (ref "R31") (pin "1") (pinfunction "1_1") (pintype "input"))
    )
    (net (code "83") (name "Net-(IR17-Pad2)") (class "Default")
      (node (ref "IR17") (pin "2") (pinfunction "2_2") (pintype "input"))
      (node (ref "R33") (pin "1") (pinfunction "1_1") (pintype "input"))
    )
    (net (code "84") (name "Net-(IR18-Pad2)") (class "Default")
      (node (ref "IR18") (pin "2") (pinfunction "2_2") (pintype "input"))
      (node (ref "R35") (pin "1") (pinfunction "1_1") (pintype "input"))
    )
    (net (code "85") (name "Net-(IR19-Pad2)") (class "Default")
      (node (ref "IR19") (pin "2") (pinfunction "2_2") (pintype "input"))
      (node (ref "R37") (pin "1") (pinfunction "1_1") (pintype "input"))
    )
    (net (code "86") (name "Net-(IR20-Pad2)") (class "Default")
      (node (ref "IR20") (pin "2") (pinfunction "2_2") (pintype "input"))
      (node (ref "R39") (pin "1") (pinfunction "1_1") (pintype "input"))
    )
    (net (code "87") (name "Net-(IR21-Pad2)") (class "Default")
      (node (ref "IR21") (pin "2") (pinfunction "2_2") (pintype "input"))
      (node (ref "R41") (pin "1") (pinfunction "1_1") (pintype "input"))
    )
    (net (code "88") (name "Net-(IR22-Pad2)") (class "Default")
      (node (ref "IR22") (pin "2") (pinfunction "2_2") (pintype "input"))
      (node (ref "R43") (pin "1") (pinfunction "1_1") (pintype "input"))
    )
    (net (code "89") (name "Net-(IR23-Pad2)") (class "Default")
      (node (ref "IR23") (pin "2") (pinfunction "2_2") (pintype "input"))
      (node (ref "R45") (pin "1") (pinfunction "1_1") (pintype "input"))
    )
    (net (code "90") (name "Net-(IR24-Pad2)") (class "Default")
      (node (ref "IR24") (pin "2") (pinfunction "2_2") (pintype "input"))
      (node (ref "R47") (pin "1") (pinfunction "1_1") (pintype "input"))
    )
    (net (code "91") (name "Net-(IR25-Pad2)") (class "Default")
      (node (ref "IR25") (pin "2") (pinfunction "2_2") (pintype "input"))
      (node (ref "R49") (pin "1") (pinfunction "1_1") (pintype "input"))
    )
    (net (code "92") (name "Net-(IR26-Pad2)") (class "Default")
      (node (ref "IR26") (pin "2") (pinfunction "2_2") (pintype "input"))
      (node (ref "R51") (pin "1") (pinfunction "1_1") (pintype "input"))
    )
    (net (code "93") (name "Net-(IR27-Pad2)") (class "Default")
      (node (ref "IR27") (pin "2") (pinfunction "2_2") (pintype "input"))
      (node (ref "R53") (pin "1") (pinfunction "1_1") (pintype "input"))
    )
    (net (code "94") (name "Net-(IR28-Pad2)") (class "Default")
      (node (ref "IR28") (pin "2") (pinfunction "2_2") (pintype "input"))
      (node (ref "R55") (pin "1") (pinfunction "1_1") (pintype "input"))
    )
    (net (code "95") (name "Net-(IR29-Pad2)") (class "Default")
      (node (ref "IR29") (pin "2") (pinfunction "2_2") (pintype "input"))
      (node (ref "R57") (pin "1") (pinfunction "1_1") (pintype "input"))
    )
    (net (code "96") (name "Net-(IR30-Pad2)") (class "Default")
      (node (ref "IR30") (pin "2") (pinfunction "2_2") (pintype "input"))
      (node (ref "R59") (pin "1") (pinfunction "1_1") (pintype "input"))
    )
    (net (code "97") (name "Net-(IR31-Pad2)") (class "Default")
      (node (ref "IR31") (pin "2") (pinfunction "2_2") (pintype "input"))
      (node (ref "R95") (pin "1") (pinfunction "1_1") (pintype "input"))
    )
    (net (code "98") (name "Net-(IR32-Pad2)") (class "Default")
      (node (ref "IR32") (pin "2") (pinfunction "2_2") (pintype "input"))
      (node (ref "R97") (pin "1") (pinfunction "1_1") (pintype "input"))
    )
    (net (code "99") (name "Net-(LED1-A)") (class "Default")
      (node (ref "LED1") (pin "2") (pinfunction "A_2") (pintype "input"))
      (node (ref "R63") (pin "1") (pinfunction "1_1") (pintype "input"))
    )
    (net (code "100") (name "Net-(LED2-A)") (class "Default")
      (node (ref "LED2") (pin "2") (pinfunction "A_2") (pintype "input"))
      (node (ref "R64") (pin "1") (pinfunction "1_1") (pintype "input"))
    )
    (net (code "101") (name "Net-(LED3-A)") (class "Default")
      (node (ref "LED3") (pin "2") (pinfunction "A_2") (pintype "input"))
      (node (ref "R65") (pin "1") (pinfunction "1_1") (pintype "input"))
    )
    (net (code "102") (name "Net-(LED4-A)") (class "Default")
      (node (ref "LED4") (pin "2") (pinfunction "A_2") (pintype "input"))
      (node (ref "R66") (pin "1") (pinfunction "1_1") (pintype "input"))
    )
    (net (code "103") (name "Net-(LED5-A)") (class "Default")
      (node (ref "LED5") (pin "2") (pinfunction "A_2") (pintype "input"))
      (node (ref "R67") (pin "1") (pinfunction "1_1") (pintype "input"))
    )
    (net (code "104") (name "Net-(LED6-A)") (class "Default")
      (node (ref "LED6") (pin "2") (pinfunction "A_2") (pintype "input"))
      (node (ref "R68") (pin "1") (pinfunction "1_1") (pintype "input"))
    )
    (net (code "105") (name "Net-(LED7-A)") (class "Default")
      (node (ref "LED7") (pin "2") (pinfunction "A_2") (pintype "input"))
      (node (ref "R69") (pin "1") (pinfunction "1_1") (pintype "input"))
    )
    (net (code "106") (name "Net-(LED8-A)") (class "Default")
      (node (ref "LED8") (pin "2") (pinfunction "A_2") (pintype "input"))
      (node (ref "R70") (pin "1") (pinfunction "1_1") (pintype "input"))
    )
    (net (code "107") (name "Net-(LED9-A)") (class "Default")
      (node (ref "LED9") (pin "2") (pinfunction "A_2") (pintype "input"))
      (node (ref "R71") (pin "1") (pinfunction "1_1") (pintype "input"))
    )
    (net (code "108") (name "Net-(LED10-A)") (class "Default")
      (node (ref "LED10") (pin "2") (pinfunction "A_2") (pintype "input"))
      (node (ref "R72") (pin "1") (pinfunction "1_1") (pintype "input"))
    )
    (net (code "109") (name "Net-(LED11-A)") (class "Default")
      (node (ref "LED11") (pin "2") (pinfunction "A_2") (pintype "input"))
      (node (ref "R73") (pin "1") (pinfunction "1_1") (pintype "input"))
    )
    (net (code "110") (name "Net-(LED12-A)") (class "Default")
      (node (ref "LED12") (pin "2") (pinfunction "A_2") (pintype "input"))
      (node (ref "R74") (pin "1") (pinfunction "1_1") (pintype "input"))
    )
    (net (code "111") (name "Net-(LED13-A)") (class "Default")
      (node (ref "LED13") (pin "2") (pinfunction "A_2") (pintype "input"))
      (node (ref "R75") (pin "1") (pinfunction "1_1") (pintype "input"))
    )
    (net (code "112") (name "Net-(LED14-A)") (class "Default")
      (node (ref "LED14") (pin "2") (pinfunction "A_2") (pintype "input"))
      (node (ref "R76") (pin "1") (pinfunction "1_1") (pintype "input"))
    )
    (net (code "113") (name "Net-(LED15-A)") (class "Default")
      (node (ref "LED15") (pin "2") (pinfunction "A_2") (pintype "input"))
      (node (ref "R77") (pin "1") (pinfunction "1_1") (pintype "input"))
    )
    (net (code "114") (name "Net-(LED16-A)") (class "Default")
      (node (ref "LED16") (pin "2") (pinfunction "A_2") (pintype "input"))
      (node (ref "R78") (pin "1") (pinfunction "1_1") (pintype "input"))
    )
    (net (code "115") (name "Net-(LED17-A)") (class "Default")
      (node (ref "LED17") (pin "2") (pinfunction "A_2") (pintype "input"))
      (node (ref "R79") (pin "1") (pinfunction "1_1") (pintype "input"))
    )
    (net (code "116") (name "Net-(LED18-A)") (class "Default")
      (node (ref "LED18") (pin "2") (pinfunction "A_2") (pintype "input"))
      (node (ref "R80") (pin "1") (pinfunction "1_1") (pintype "input"))
    )
    (net (code "117") (name "Net-(LED19-A)") (class "Default")
      (node (ref "LED19") (pin "2") (pinfunction "A_2") (pintype "input"))
      (node (ref "R81") (pin "1") (pinfunction "1_1") (pintype "input"))
    )
    (net (code "118") (name "Net-(LED20-A)") (class "Default")
      (node (ref "LED20") (pin "2") (pinfunction "A_2") (pintype "input"))
      (node (ref "R82") (pin "1") (pinfunction "1_1") (pintype "input"))
    )
    (net (code "119") (name "Net-(LED21-A)") (class "Default")
      (node (ref "LED21") (pin "2") (pinfunction "A_2") (pintype "input"))
      (node (ref "R83") (pin "1") (pinfunction "1_1") (pintype "input"))
    )
    (net (code "120") (name "Net-(LED22-A)") (class "Default")
      (node (ref "LED22") (pin "2") (pinfunction "A_2") (pintype "input"))
      (node (ref "R84") (pin "1") (pinfunction "1_1") (pintype "input"))
    )
    (net (code "121") (name "Net-(LED23-A)") (class "Default")
      (node (ref "LED23") (pin "2") (pinfunction "A_2") (pintype "input"))
      (node (ref "R85") (pin "1") (pinfunction "1_1") (pintype "input"))
    )
    (net (code "122") (name "Net-(LED24-A)") (class "Default")
      (node (ref "LED24") (pin "2") (pinfunction "A_2") (pintype "input"))
      (node (ref "R86") (pin "1") (pinfunction "1_1") (pintype "input"))
    )
    (net (code "123") (name "Net-(LED25-A)") (class "Default")
      (node (ref "LED25") (pin "2") (pinfunction "A_2") (pintype "input"))
      (node (ref "R87") (pin "1") (pinfunction "1_1") (pintype "input"))
    )
    (net (code "124") (name "Net-(LED26-A)") (class "Default")
      (node (ref "LED26") (pin "2") (pinfunction "A_2") (pintype "input"))
      (node (ref "R88") (pin "1") (pinfunction "1_1") (pintype "input"))
    )
    (net (code "125") (name "Net-(LED27-A)") (class "Default")
      (node (ref "LED27") (pin "2") (pinfunction "A_2") (pintype "input"))
      (node (ref "R89") (pin "1") (pinfunction "1_1") (pintype "input"))
    )
    (net (code "126") (name "Net-(LED28-A)") (class "Default")
      (node (ref "LED28") (pin "2") (pinfunction "A_2") (pintype "input"))
      (node (ref "R90") (pin "1") (pinfunction "1_1") (pintype "input"))
    )
    (net (code "127") (name "Net-(LED29-A)") (class "Default")
      (node (ref "LED29") (pin "2") (pinfunction "A_2") (pintype "input"))
      (node (ref "R91") (pin "1") (pinfunction "1_1") (pintype "input"))
    )
    (net (code "128") (name "Net-(LED30-A)") (class "Default")
      (node (ref "LED30") (pin "2") (pinfunction "A_2") (pintype "input"))
      (node (ref "R92") (pin "1") (pinfunction "1_1") (pintype "input"))
    )
    (net (code "129") (name "Net-(LED31-A)") (class "Default")
      (node (ref "LED31") (pin "2") (pinfunction "A_2") (pintype "input"))
      (node (ref "R93") (pin "1") (pinfunction "1_1") (pintype "input"))
    )
    (net (code "130") (name "Net-(LED32-A)") (class "Default")
      (node (ref "LED32") (pin "2") (pinfunction "A_2") (pintype "input"))
      (node (ref "R94") (pin "1") (pinfunction "1_1") (pintype "input"))
    )
    (net (code "131") (name "Net-(R63-Pad2)") (class "Default")
      (node (ref "R63") (pin "2") (pinfunction "2_2") (pintype "input"))
      (node (ref "R64") (pin "2") (pinfunction "2_2") (pintype "input"))
      (node (ref "R65") (pin "2") (pinfunction "2_2") (pintype "input"))
      (node (ref "R66") (pin "2") (pinfunction "2_2") (pintype "input"))
      (node (ref "R67") (pin "2") (pinfunction "2_2") (pintype "input"))
      (node (ref "R68") (pin "2") (pinfunction "2_2") (pintype "input"))
      (node (ref "R69") (pin "2") (pinfunction "2_2") (pintype "input"))
      (node (ref "R70") (pin "2") (pinfunction "2_2") (pintype "input"))
      (node (ref "R71") (pin "2") (pinfunction "2_2") (pintype "input"))
      (node (ref "R72") (pin "2") (pinfunction "2_2") (pintype "input"))
      (node (ref "R73") (pin "2") (pinfunction "2_2") (pintype "input"))
      (node (ref "R74") (pin "2") (pinfunction "2_2") (pintype "input"))
      (node (ref "R75") (pin "2") (pinfunction "2_2") (pintype "input"))
      (node (ref "R76") (pin "2") (pinfunction "2_2") (pintype "input"))
      (node (ref "R77") (pin "2") (pinfunction "2_2") (pintype "input"))
      (node (ref "R78") (pin "2") (pinfunction "2_2") (pintype "input"))
      (node (ref "R79") (pin "2") (pinfunction "2_2") (pintype "input"))
      (node (ref "R80") (pin "2") (pinfunction "2_2") (pintype "input"))
      (node (ref "R81") (pin "2") (pinfunction "2_2") (pintype "input"))
      (node (ref "R82") (pin "2") (pinfunction "2_2") (pintype "input"))
      (node (ref "R83") (pin "2") (pinfunction "2_2") (pintype "input"))
      (node (ref "R84") (pin "2") (pinfunction "2_2") (pintype "input"))
      (node (ref "R85") (pin "2") (pinfunction "2_2") (pintype "input"))
      (node (ref "R86") (pin "2") (pinfunction "2_2") (pintype "input"))
      (node (ref "R87") (pin "2") (pinfunction "2_2") (pintype "input"))
      (node (ref "R88") (pin "2") (pinfunction "2_2") (pintype "input"))
      (node (ref "R89") (pin "2") (pinfunction "2_2") (pintype "input"))
      (node (ref "R90") (pin "2") (pinfunction "2_2") (pintype "input"))
      (node (ref "R91") (pin "2") (pinfunction "2_2") (pintype "input"))
      (node (ref "R92") (pin "2") (pinfunction "2_2") (pintype "input"))
      (node (ref "R93") (pin "2") (pinfunction "2_2") (pintype "input"))
      (node (ref "R94") (pin "2") (pinfunction "2_2") (pintype "input"))
      (node (ref "SJ3") (pin "1") (pinfunction "1_1") (pintype "input"))
    )
    (net (code "132") (name "VCC") (class "Default")
      (node (ref "C3") (pin "1") (pinfunction "1_1") (pintype "input"))
      (node (ref "C4") (pin "1") (pinfunction "1_1") (pintype "input"))
      (node (ref "C5") (pin "1") (pinfunction "1_1") (pintype "input"))
      (node (ref "C6") (pin "1") (pinfunction "1_1") (pintype "input"))
      (node (ref "C7") (pin "1") (pinfunction "1_1") (pintype "input"))
      (node (ref "C8") (pin "1") (pinfunction "1_1") (pintype "input"))
      (node (ref "IC1") (pin "20") (pinfunction "VCC_20") (pintype "input"))
      (node (ref "IC2") (pin "20") (pinfunction "VCC_20") (pintype "input"))
      (node (ref "IC3") (pin "20") (pinfunction "VCC_20") (pintype "input"))
      (node (ref "IC4") (pin "20") (pinfunction "VCC_20") (pintype "input"))
      (node (ref "SJ3") (pin "2") (pinfunction "2_2") (pintype "input"))
      (node (ref "U38") (pin "36") (pinfunction "36_36") (pintype "unspecified"))
      (node (ref "U38") (pin "37") (pinfunction "37_37") (pintype "unspecified"))
    )
    (net (code "133") (name "unconnected-(U38-Pad41)") (class "Default")
      (node (ref "U38") (pin "41") (pinfunction "41_41") (pintype "unspecified"))
    )
    (net (code "134") (name "unconnected-(U38-Pad42)") (class "Default")
      (node (ref "U38") (pin "42") (pinfunction "42_42") (pintype "unspecified"))
    )
  )
)
